# fingertip_16line_2.net
KiCad netlist of a schematic drawn in EAGLE
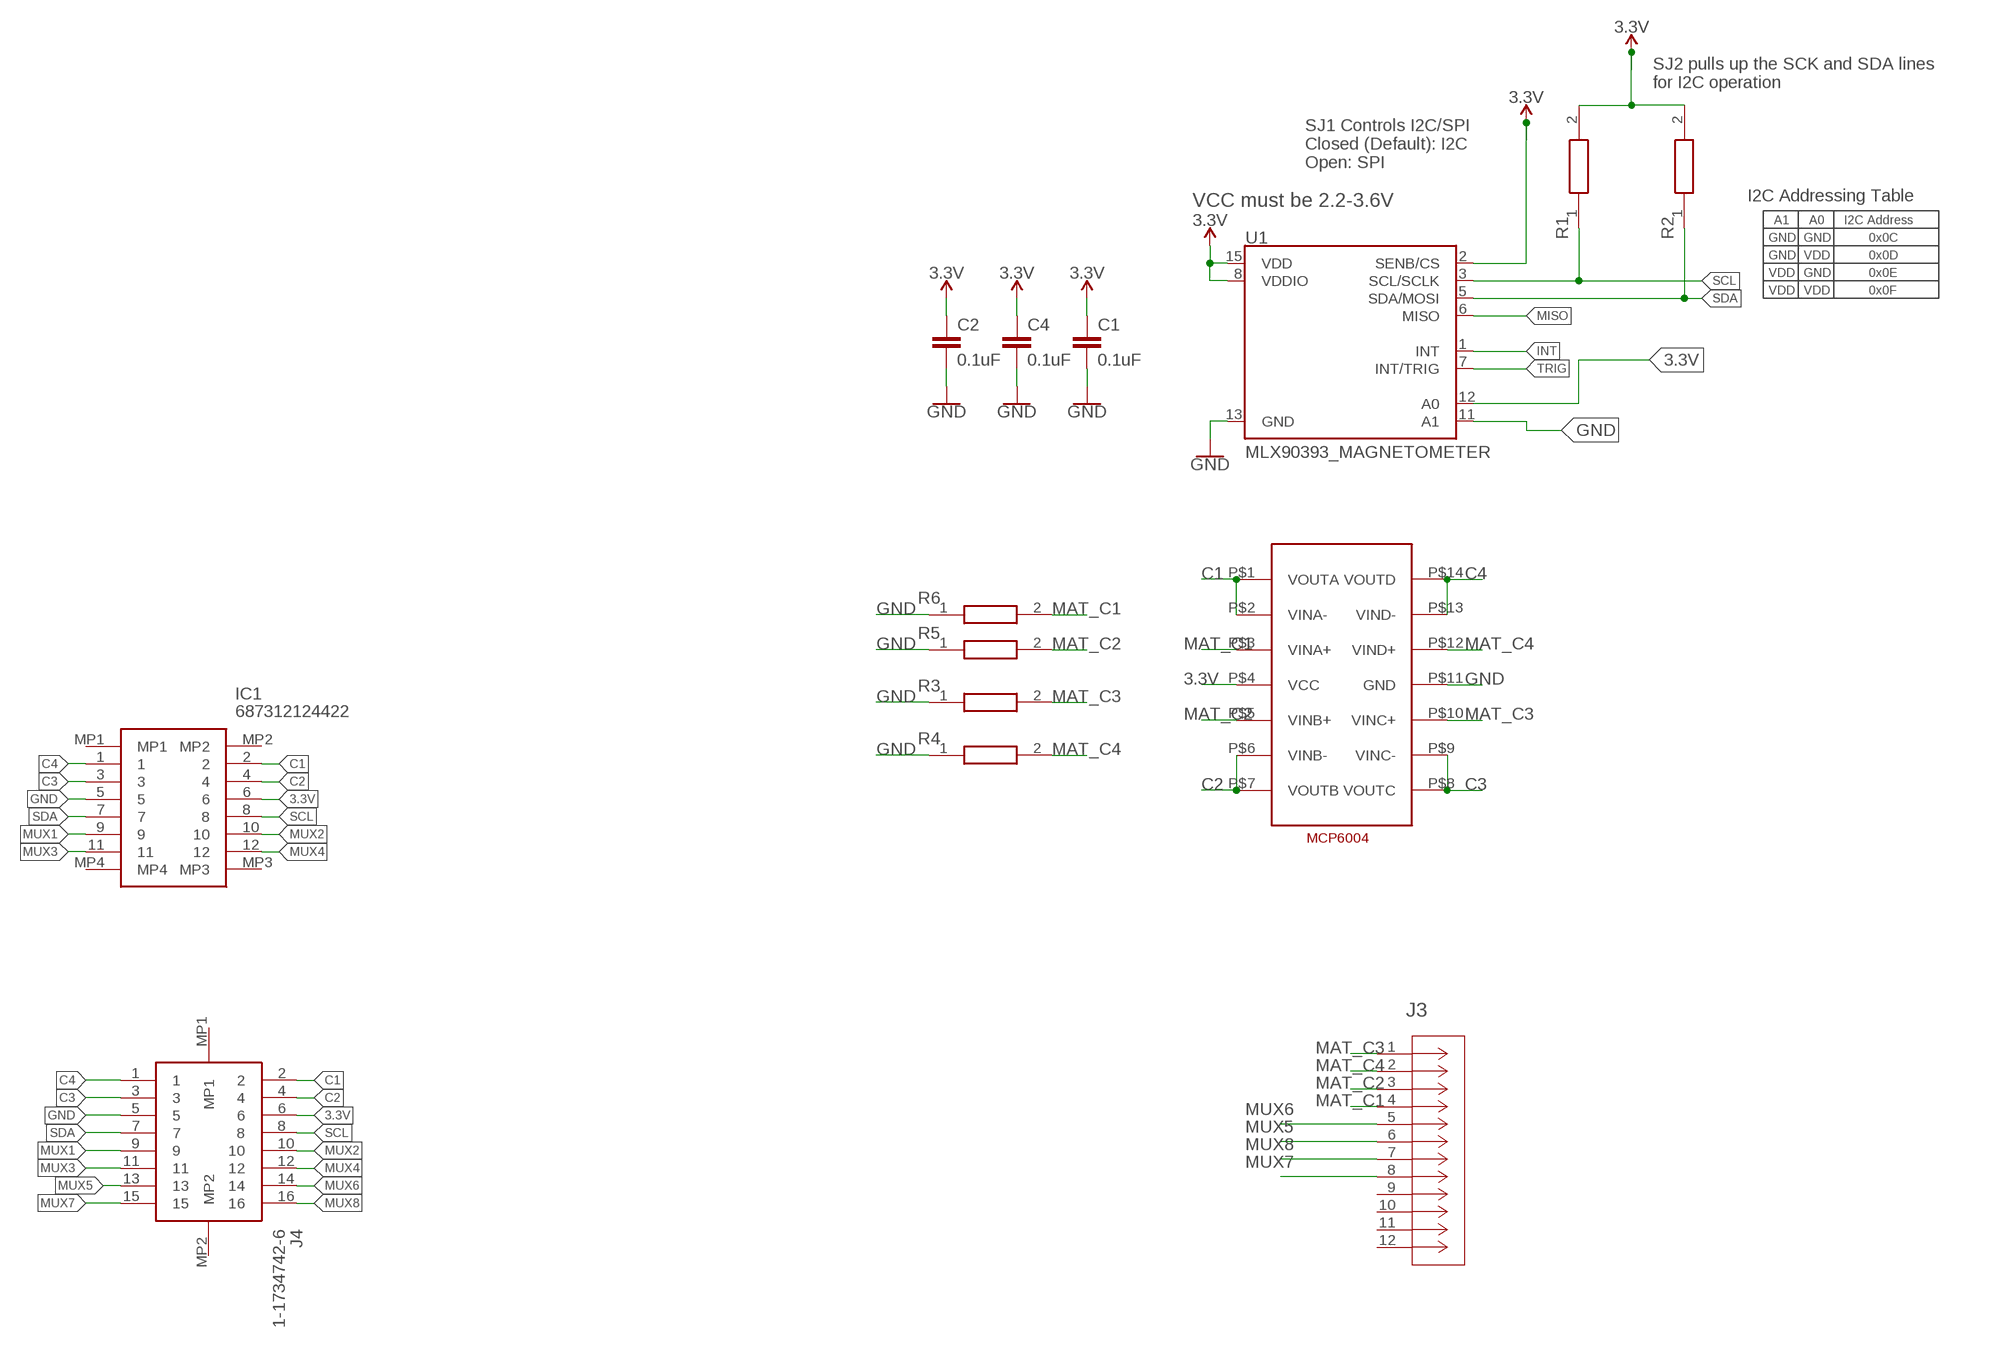
[diagram p0: schematic, sheet 1]

(export (version "E")
  (design (tool "Eeschema 10.0.6"))
  (components
    (comp (ref "C1")
      (value "0.1uF")
      (footprint "eagle-import:0402")
      (libsource (lib "eagle-import") (part "0.1UF-0402-16V-10%"))
    )
    (comp (ref "C2")
      (value "0.1uF")
      (footprint "eagle-import:0402")
      (libsource (lib "eagle-import") (part "0.1UF-0402-16V-10%"))
    )
    (comp (ref "C4")
      (value "0.1uF")
      (footprint "eagle-import:0402")
      (libsource (lib "eagle-import") (part "0.1UF-0402-16V-10%"))
    )
    (comp (ref "IC1")
      (value "687312124422")
      (footprint "eagle-import:687312124422")
      (fields (field (name "MOUSER_PART_NUMBER") "710-687312124422"))
      (libsource (lib "eagle-import") (part "687312124422"))
    )
    (comp (ref "J3")
      (value "FH12-8S-1SV(55)")
      (footprint "eagle-import:CON8_1X8_DUTB1_HRS_HIR")
      (fields (field (name "COPYRIGHT") "Copyright (C) 2018 Accelerated Designs. All rights reserved"))
      (libsource (lib "eagle-import") (part "FH12-8S-1SV(55)"))
    )
    (comp (ref "J4")
      (value "1-1734742-6")
      (footprint "eagle-import:117347426")
      (fields (field (name "MOUSER_PART_NUMBER") "571-1-1734742-6"))
      (libsource (lib "eagle-import") (part "1-1734742-6"))
    )
    (comp (ref "R1")
      (value "ERJ-S02J103X")
      (footprint "eagle-import:RESC1005X40N")
      (libsource (lib "eagle-import") (part "ERJ-S02J103X"))
    )
    (comp (ref "R2")
      (value "ERJ-S02J103X")
      (footprint "eagle-import:RESC1005X40N")
      (libsource (lib "eagle-import") (part "ERJ-S02J103X"))
    )
    (comp (ref "R3")
      (value "ERJ-S02J103X")
      (footprint "eagle-import:RESC1005X40N")
      (libsource (lib "eagle-import") (part "ERJ-S02J103X"))
    )
    (comp (ref "R4")
      (value "ERJ-S02J103X")
      (footprint "eagle-import:RESC1005X40N")
      (libsource (lib "eagle-import") (part "ERJ-S02J103X"))
    )
    (comp (ref "R5")
      (value "ERJ-S02J103X")
      (footprint "eagle-import:RESC1005X40N")
      (libsource (lib "eagle-import") (part "ERJ-S02J103X"))
    )
    (comp (ref "R6")
      (value "ERJ-S02J103X")
      (footprint "eagle-import:RESC1005X40N")
      (libsource (lib "eagle-import") (part "ERJ-S02J103X"))
    )
    (comp (ref "U$2")
      (value "DECADE-MCP6004")
      (footprint "eagle-import:DECADE-MCP6003")
      (libsource (lib "eagle-import") (part "DECADE-MCP6004"))
    )
    (comp (ref "U1")
      (value "MLX90393_MAGNETOMETER")
      (footprint "eagle-import:QFN-16_WITH_AXIES")
      (libsource (lib "eagle-import") (part "MLX90393_MAGNETOMETER"))
    )
  )
  (nets
    (net (code "1") (name "/MAT_C1") (class "Default")
      (node (ref "J3") (pin "4") (pinfunction "4_4") (pintype "passive"))
      (node (ref "R6") (pin "2") (pinfunction "2_2") (pintype "bidirectional"))
      (node (ref "U$2") (pin "P$3") (pinfunction "VINA+_P$3") (pintype "bidirectional"))
    )
    (net (code "2") (name "/MAT_C2") (class "Default")
      (node (ref "J3") (pin "3") (pinfunction "3_3") (pintype "passive"))
      (node (ref "R5") (pin "2") (pinfunction "2_2") (pintype "bidirectional"))
      (node (ref "U$2") (pin "P$5") (pinfunction "VINB+_P$5") (pintype "bidirectional"))
    )
    (net (code "3") (name "/MAT_C3") (class "Default")
      (node (ref "J3") (pin "1") (pinfunction "1_1") (pintype "passive"))
      (node (ref "R3") (pin "2") (pinfunction "2_2") (pintype "bidirectional"))
      (node (ref "U$2") (pin "P$10") (pinfunction "VINC+_P$10") (pintype "bidirectional"))
    )
    (net (code "4") (name "/MAT_C4") (class "Default")
      (node (ref "J3") (pin "2") (pinfunction "2_2") (pintype "passive"))
      (node (ref "R4") (pin "2") (pinfunction "2_2") (pintype "bidirectional"))
      (node (ref "U$2") (pin "P$12") (pinfunction "VIND+_P$12") (pintype "bidirectional"))
    )
    (net (code "5") (name "3.3V") (class "Default")
      (node (ref "C1") (pin "1") (pinfunction "1_1") (pintype "passive"))
      (node (ref "C2") (pin "1") (pinfunction "1_1") (pintype "passive"))
      (node (ref "C4") (pin "1") (pinfunction "1_1") (pintype "passive"))
      (node (ref "IC1") (pin "6") (pinfunction "6_6") (pintype "bidirectional"))
      (node (ref "J4") (pin "6") (pinfunction "6_6") (pintype "bidirectional"))
      (node (ref "R1") (pin "2") (pinfunction "2_2") (pintype "bidirectional"))
      (node (ref "R2") (pin "2") (pinfunction "2_2") (pintype "bidirectional"))
      (node (ref "U$2") (pin "P$4") (pinfunction "VCC_P$4") (pintype "bidirectional"))
      (node (ref "U1") (pin "12") (pinfunction "A0_12") (pintype "bidirectional"))
      (node (ref "U1") (pin "15") (pinfunction "VDD_15") (pintype "bidirectional"))
      (node (ref "U1") (pin "2") (pinfunction "SENB/CS_2") (pintype "bidirectional"))
      (node (ref "U1") (pin "8") (pinfunction "VDDIO_8") (pintype "bidirectional"))
    )
    (net (code "6") (name "C1") (class "Default")
      (node (ref "IC1") (pin "2") (pinfunction "2_2") (pintype "bidirectional"))
      (node (ref "J4") (pin "2") (pinfunction "2_2") (pintype "bidirectional"))
      (node (ref "U$2") (pin "P$1") (pinfunction "VOUTA_P$1") (pintype "bidirectional"))
      (node (ref "U$2") (pin "P$2") (pinfunction "VINA-_P$2") (pintype "bidirectional"))
    )
    (net (code "7") (name "C2") (class "Default")
      (node (ref "IC1") (pin "4") (pinfunction "4_4") (pintype "bidirectional"))
      (node (ref "J4") (pin "4") (pinfunction "4_4") (pintype "bidirectional"))
      (node (ref "U$2") (pin "P$6") (pinfunction "VINB-_P$6") (pintype "bidirectional"))
      (node (ref "U$2") (pin "P$7") (pinfunction "VOUTB_P$7") (pintype "bidirectional"))
    )
    (net (code "8") (name "C3") (class "Default")
      (node (ref "IC1") (pin "3") (pinfunction "3_3") (pintype "bidirectional"))
      (node (ref "J4") (pin "3") (pinfunction "3_3") (pintype "bidirectional"))
      (node (ref "U$2") (pin "P$8") (pinfunction "VOUTC_P$8") (pintype "bidirectional"))
      (node (ref "U$2") (pin "P$9") (pinfunction "VINC-_P$9") (pintype "bidirectional"))
    )
    (net (code "9") (name "C4") (class "Default")
      (node (ref "IC1") (pin "1") (pinfunction "1_1") (pintype "bidirectional"))
      (node (ref "J4") (pin "1") (pinfunction "1_1") (pintype "bidirectional"))
      (node (ref "U$2") (pin "P$13") (pinfunction "VIND-_P$13") (pintype "bidirectional"))
      (node (ref "U$2") (pin "P$14") (pinfunction "VOUTD_P$14") (pintype "bidirectional"))
    )
    (net (code "10") (name "GND") (class "Default")
      (node (ref "C1") (pin "2") (pinfunction "2_2") (pintype "passive"))
      (node (ref "C2") (pin "2") (pinfunction "2_2") (pintype "passive"))
      (node (ref "C4") (pin "2") (pinfunction "2_2") (pintype "passive"))
      (node (ref "IC1") (pin "5") (pinfunction "5_5") (pintype "bidirectional"))
      (node (ref "J4") (pin "5") (pinfunction "5_5") (pintype "bidirectional"))
      (node (ref "R3") (pin "1") (pinfunction "1_1") (pintype "bidirectional"))
      (node (ref "R4") (pin "1") (pinfunction "1_1") (pintype "bidirectional"))
      (node (ref "R5") (pin "1") (pinfunction "1_1") (pintype "bidirectional"))
      (node (ref "R6") (pin "1") (pinfunction "1_1") (pintype "bidirectional"))
      (node (ref "U$2") (pin "P$11") (pinfunction "GND_P$11") (pintype "bidirectional"))
      (node (ref "U1") (pin "11") (pinfunction "A1_11") (pintype "bidirectional"))
      (node (ref "U1") (pin "13") (pinfunction "GND_13") (pintype "bidirectional"))
    )
    (net (code "11") (name "INT") (class "Default")
      (node (ref "U1") (pin "1") (pinfunction "INT_1") (pintype "bidirectional"))
    )
    (net (code "12") (name "MISO") (class "Default")
      (node (ref "U1") (pin "6") (pinfunction "MISO_6") (pintype "bidirectional"))
    )
    (net (code "13") (name "MUX1") (class "Default")
      (node (ref "IC1") (pin "9") (pinfunction "9_9") (pintype "bidirectional"))
      (node (ref "J4") (pin "9") (pinfunction "9_9") (pintype "bidirectional"))
    )
    (net (code "14") (name "MUX2") (class "Default")
      (node (ref "IC1") (pin "10") (pinfunction "10_10") (pintype "bidirectional"))
      (node (ref "J4") (pin "10") (pinfunction "10_10") (pintype "bidirectional"))
    )
    (net (code "15") (name "MUX3") (class "Default")
      (node (ref "IC1") (pin "11") (pinfunction "11_11") (pintype "bidirectional"))
      (node (ref "J4") (pin "11") (pinfunction "11_11") (pintype "bidirectional"))
    )
    (net (code "16") (name "MUX4") (class "Default")
      (node (ref "IC1") (pin "12") (pinfunction "12_12") (pintype "bidirectional"))
      (node (ref "J4") (pin "12") (pinfunction "12_12") (pintype "bidirectional"))
    )
    (net (code "17") (name "MUX5") (class "Default")
      (node (ref "J3") (pin "6") (pinfunction "6_6") (pintype "passive"))
      (node (ref "J4") (pin "13") (pinfunction "13_13") (pintype "bidirectional"))
    )
    (net (code "18") (name "MUX6") (class "Default")
      (node (ref "J3") (pin "5") (pinfunction "5_5") (pintype "passive"))
      (node (ref "J4") (pin "14") (pinfunction "14_14") (pintype "bidirectional"))
    )
    (net (code "19") (name "MUX7") (class "Default")
      (node (ref "J3") (pin "8") (pinfunction "8_8") (pintype "passive"))
      (node (ref "J4") (pin "15") (pinfunction "15_15") (pintype "bidirectional"))
    )
    (net (code "20") (name "MUX8") (class "Default")
      (node (ref "J3") (pin "7") (pinfunction "7_7") (pintype "passive"))
      (node (ref "J4") (pin "16") (pinfunction "16_16") (pintype "bidirectional"))
    )
    (net (code "21") (name "SCL") (class "Default")
      (node (ref "IC1") (pin "8") (pinfunction "8_8") (pintype "bidirectional"))
      (node (ref "J4") (pin "8") (pinfunction "8_8") (pintype "bidirectional"))
      (node (ref "R1") (pin "1") (pinfunction "1_1") (pintype "bidirectional"))
      (node (ref "U1") (pin "3") (pinfunction "SCL/SCLK_3") (pintype "bidirectional"))
    )
    (net (code "22") (name "SDA") (class "Default")
      (node (ref "IC1") (pin "7") (pinfunction "7_7") (pintype "bidirectional"))
      (node (ref "J4") (pin "7") (pinfunction "7_7") (pintype "bidirectional"))
      (node (ref "R2") (pin "1") (pinfunction "1_1") (pintype "bidirectional"))
      (node (ref "U1") (pin "5") (pinfunction "SDA/MOSI_5") (pintype "bidirectional"))
    )
    (net (code "23") (name "TRIG") (class "Default")
      (node (ref "U1") (pin "7") (pinfunction "INT/TRIG_7") (pintype "bidirectional"))
    )
    (net (code "24") (name "unconnected-(IC1-PadMP1)") (class "Default")
      (node (ref "IC1") (pin "MP1") (pinfunction "MP1_MP1") (pintype "bidirectional"))
    )
    (net (code "25") (name "unconnected-(IC1-PadMP2)") (class "Default")
      (node (ref "IC1") (pin "MP2") (pinfunction "MP2_MP2") (pintype "bidirectional"))
    )
    (net (code "26") (name "unconnected-(IC1-PadMP3)") (class "Default")
      (node (ref "IC1") (pin "MP3") (pinfunction "MP3_MP3") (pintype "bidirectional"))
    )
    (net (code "27") (name "unconnected-(IC1-PadMP4)") (class "Default")
      (node (ref "IC1") (pin "MP4") (pinfunction "MP4_MP4") (pintype "bidirectional"))
    )
    (net (code "28") (name "unconnected-(J3-Pad9)") (class "Default")
      (node (ref "J3") (pin "9") (pinfunction "9_9") (pintype "passive"))
    )
    (net (code "29") (name "unconnected-(J3-Pad10)") (class "Default")
      (node (ref "J3") (pin "10") (pinfunction "10_10") (pintype "passive"))
    )
    (net (code "30") (name "unconnected-(J3-Pad11)") (class "Default")
      (node (ref "J3") (pin "11") (pinfunction "11_11") (pintype "passive"))
    )
    (net (code "31") (name "unconnected-(J3-Pad12)") (class "Default")
      (node (ref "J3") (pin "12") (pinfunction "12_12") (pintype "passive"))
    )
    (net (code "32") (name "unconnected-(J4-PadMP1)") (class "Default")
      (node (ref "J4") (pin "MP1") (pinfunction "MP1_MP1") (pintype "bidirectional"))
    )
    (net (code "33") (name "unconnected-(J4-PadMP2)") (class "Default")
      (node (ref "J4") (pin "MP2") (pinfunction "MP2_MP2") (pintype "bidirectional"))
    )
  )
)
